# single_trigger_in_board.net
KiCad netlist of a schematic drawn in EAGLE
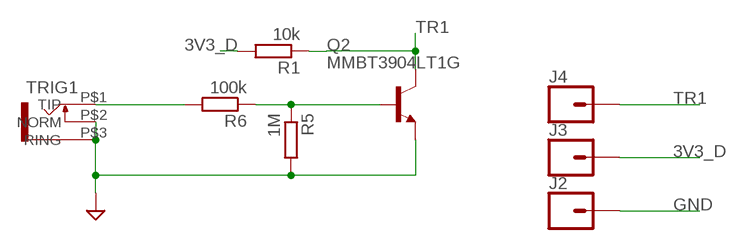
[diagram p0: schematic, sheet 1]

(export (version "E")
  (design (tool "Eeschema 10.0.6"))
  (components
    (comp (ref "J2")
      (value "CONN_01")
      (footprint "eagle-import:1X01")
      (libsource (lib "eagle-import") (part "CONN_01"))
    )
    (comp (ref "J3")
      (value "CONN_01")
      (footprint "eagle-import:1X01")
      (libsource (lib "eagle-import") (part "CONN_01"))
    )
    (comp (ref "J4")
      (value "CONN_01")
      (footprint "eagle-import:1X01")
      (libsource (lib "eagle-import") (part "CONN_01"))
    )
    (comp (ref "Q2")
      (value "MMBT3904LT1G")
      (footprint "eagle-import:TRANSISTOR_SOT23-BEC")
      (libsource (lib "eagle-import") (part "TRANSISTOR_-NPN-SOT23-BECMMBT3904LT1"))
    )
    (comp (ref "R1")
      (value "10k")
      (footprint "eagle-import:R0603")
      (libsource (lib "eagle-import") (part "R-EU_R0603"))
    )
    (comp (ref "R5")
      (value "1M")
      (footprint "eagle-import:R0603")
      (libsource (lib "eagle-import") (part "R-EU_R0603"))
    )
    (comp (ref "R6")
      (value "100k")
      (footprint "eagle-import:R0603")
      (libsource (lib "eagle-import") (part "R-EU_R0603"))
    )
    (comp (ref "TRIG1")
      (value "JACK_KOBICONN_PJM301DM_V2")
      (footprint "eagle-import:KOBICONN_PJM301DM_JACK")
      (libsource (lib "eagle-import") (part "JACK_KOBICONN_PJM301DM_V2"))
    )
  )
  (nets
    (net (code "1") (name "/3V3_D") (class "Default")
      (node (ref "J3") (pin "1") (pinfunction "1_1") (pintype "passive"))
      (node (ref "R1") (pin "2") (pinfunction "2_2") (pintype "passive"))
    )
    (net (code "2") (name "/TR1") (class "Default")
      (node (ref "J4") (pin "1") (pinfunction "1_1") (pintype "passive"))
      (node (ref "Q2") (pin "C") (pinfunction "C_C") (pintype "passive"))
      (node (ref "R1") (pin "1") (pinfunction "1_1") (pintype "passive"))
    )
    (net (code "3") (name "GND") (class "Default")
      (node (ref "J2") (pin "1") (pinfunction "1_1") (pintype "passive"))
      (node (ref "Q2") (pin "E") (pinfunction "E_E") (pintype "passive"))
      (node (ref "R5") (pin "2") (pinfunction "2_2") (pintype "passive"))
      (node (ref "TRIG1") (pin "P$2") (pinfunction "NORM_P$2") (pintype "passive"))
      (node (ref "TRIG1") (pin "P$3") (pinfunction "RING_P$3") (pintype "passive"))
    )
    (net (code "4") (name "Net-(Q2-PadB)") (class "Default")
      (node (ref "Q2") (pin "B") (pinfunction "B_B") (pintype "passive"))
      (node (ref "R5") (pin "1") (pinfunction "1_1") (pintype "passive"))
      (node (ref "R6") (pin "1") (pinfunction "1_1") (pintype "passive"))
    )
    (net (code "5") (name "Net-(TRIG1-TIP)") (class "Default")
      (node (ref "R6") (pin "2") (pinfunction "2_2") (pintype "passive"))
      (node (ref "TRIG1") (pin "P$1") (pinfunction "TIP_P$1") (pintype "passive"))
    )
  )
)
